# UI.net
KiCad netlist of a schematic drawn in Altium Designer
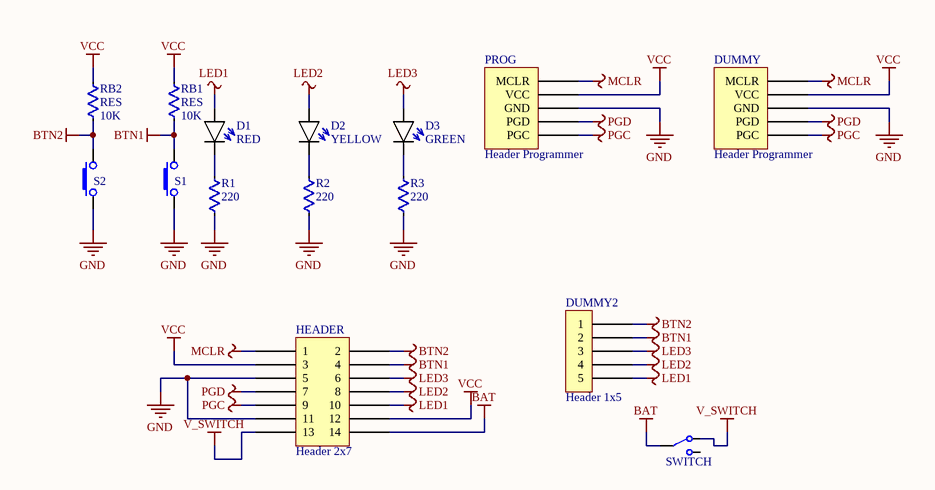
[diagram p0: UI.SchDoc]

(export (version "E")
  (design (tool "Eeschema 10.0.6"))
  (components
    (comp (ref "D1")
      (value "LED")
      (footprint "LED-3MM-RED")
      (fields (field (name "COLOR") "RED"))
      (libsource (lib "AltiumLibrary") (part "LED"))
    )
    (comp (ref "D2")
      (value "LED")
      (footprint "LED-3MM-YELLOW")
      (fields (field (name "COLOR") "YELLOW"))
      (libsource (lib "AltiumLibrary") (part "LED"))
    )
    (comp (ref "D3")
      (value "LED")
      (footprint "LED-3MM-GREEN")
      (fields (field (name "COLOR") "GREEN"))
      (libsource (lib "AltiumLibrary") (part "LED"))
    )
    (comp (ref "DUMMY")
      (value "Header Programmer")
      (footprint "Header 1x5")
      (libsource (lib "AltiumLibrary") (part "Header Programmer"))
    )
    (comp (ref "DUMMY2")
      (value "Header 1x5")
      (footprint "Header 1x5")
      (libsource (lib "AltiumLibrary") (part "Header 1x5"))
    )
    (comp (ref "HEADER")
      (value "Header 2x7")
      (footprint "HEADER 2x7")
      (libsource (lib "AltiumLibrary") (part "Header 2x7"))
    )
    (comp (ref "PROG")
      (value "Header Programmer")
      (footprint "Header 1x5")
      (libsource (lib "AltiumLibrary") (part "Header Programmer"))
    )
    (comp (ref "R1")
      (value "220")
      (footprint "RES-Axial-400mil")
      (fields (field (name "Comment") "RES"))
      (libsource (lib "AltiumLibrary") (part "RES"))
    )
    (comp (ref "R2")
      (value "220")
      (footprint "RES-Axial-400mil")
      (fields (field (name "Comment") "RES"))
      (libsource (lib "AltiumLibrary") (part "RES"))
    )
    (comp (ref "R3")
      (value "220")
      (footprint "RES-Axial-400mil")
      (fields (field (name "Comment") "RES"))
      (libsource (lib "AltiumLibrary") (part "RES"))
    )
    (comp (ref "RB1")
      (value "RES")
      (footprint "RES-Axial-400mil")
      (fields (field (name "ALTIUM_VALUE") "10K"))
      (libsource (lib "AltiumLibrary") (part "RES"))
    )
    (comp (ref "RB2")
      (value "RES")
      (footprint "RES-Axial-400mil")
      (fields (field (name "ALTIUM_VALUE") "10K"))
      (libsource (lib "AltiumLibrary") (part "RES"))
    )
    (comp (ref "S1")
      (value "BUTTON_SMALL_4PIN")
      (footprint "TACT_SWITCH-SMALL-4PIN")
      (libsource (lib "AltiumLibrary") (part "BUTTON_SMALL_4PIN"))
    )
    (comp (ref "S2")
      (value "BUTTON_SMALL_4PIN")
      (footprint "TACT_SWITCH-SMALL-4PIN")
      (libsource (lib "AltiumLibrary") (part "BUTTON_SMALL_4PIN"))
    )
    (comp (ref "SWITCH")
      (value "SLIDE-SWITCH")
      (footprint "SWITCH")
      (libsource (lib "AltiumLibrary") (part "SLIDE-SWITCH"))
    )
  )
  (nets
    (net (code "1") (name "BAT") (class "Default")
      (node (ref "HEADER") (pin "14") (pinfunction "14_14") (pintype "passive"))
      (node (ref "SWITCH") (pin "2") (pintype "power_in"))
    )
    (net (code "2") (name "BTN1") (class "Default")
      (node (ref "DUMMY2") (pin "2") (pinfunction "2_2") (pintype "passive"))
      (node (ref "HEADER") (pin "4") (pinfunction "4_4") (pintype "passive"))
      (node (ref "RB1") (pin "1") (pintype "passive"))
      (node (ref "S1") (pin "2") (pintype "passive"))
    )
    (net (code "3") (name "BTN2") (class "Default")
      (node (ref "DUMMY2") (pin "1") (pinfunction "1_1") (pintype "passive"))
      (node (ref "HEADER") (pin "2") (pinfunction "2_2") (pintype "passive"))
      (node (ref "RB2") (pin "1") (pintype "passive"))
      (node (ref "S2") (pin "2") (pintype "passive"))
    )
    (net (code "4") (name "GND") (class "Default")
      (node (ref "DUMMY") (pin "3") (pinfunction "GND_3") (pintype "power_in"))
      (node (ref "HEADER") (pin "11") (pinfunction "11_11") (pintype "passive"))
      (node (ref "HEADER") (pin "5") (pinfunction "5_5") (pintype "passive"))
      (node (ref "PROG") (pin "3") (pinfunction "GND_3") (pintype "power_in"))
      (node (ref "R1") (pin "1") (pintype "passive"))
      (node (ref "R2") (pin "1") (pintype "passive"))
      (node (ref "R3") (pin "1") (pintype "passive"))
      (node (ref "S1") (pin "1") (pintype "passive"))
      (node (ref "S2") (pin "1") (pintype "passive"))
    )
    (net (code "5") (name "LED1") (class "Default")
      (node (ref "D1") (pin "A") (pintype "passive"))
      (node (ref "DUMMY2") (pin "5") (pinfunction "5_5") (pintype "passive"))
      (node (ref "HEADER") (pin "10") (pinfunction "10_10") (pintype "passive"))
    )
    (net (code "6") (name "LED2") (class "Default")
      (node (ref "D2") (pin "A") (pintype "passive"))
      (node (ref "DUMMY2") (pin "4") (pinfunction "4_4") (pintype "passive"))
      (node (ref "HEADER") (pin "8") (pinfunction "8_8") (pintype "passive"))
    )
    (net (code "7") (name "LED3") (class "Default")
      (node (ref "D3") (pin "A") (pintype "passive"))
      (node (ref "DUMMY2") (pin "3") (pinfunction "3_3") (pintype "passive"))
      (node (ref "HEADER") (pin "6") (pinfunction "6_6") (pintype "passive"))
    )
    (net (code "8") (name "MCLR") (class "Default")
      (node (ref "DUMMY") (pin "1") (pinfunction "MCLR_1") (pintype "passive"))
      (node (ref "HEADER") (pin "1") (pinfunction "1_1") (pintype "passive"))
      (node (ref "PROG") (pin "1") (pinfunction "MCLR_1") (pintype "passive"))
    )
    (net (code "9") (name "Net-(D1-PadK)") (class "Default")
      (node (ref "D1") (pin "K") (pintype "passive"))
      (node (ref "R1") (pin "2") (pintype "passive"))
    )
    (net (code "10") (name "Net-(D2-PadK)") (class "Default")
      (node (ref "D2") (pin "K") (pintype "passive"))
      (node (ref "R2") (pin "2") (pintype "passive"))
    )
    (net (code "11") (name "Net-(D3-PadK)") (class "Default")
      (node (ref "D3") (pin "K") (pintype "passive"))
      (node (ref "R3") (pin "2") (pintype "passive"))
    )
    (net (code "12") (name "PGC") (class "Default")
      (node (ref "DUMMY") (pin "5") (pinfunction "PGC_5") (pintype "passive"))
      (node (ref "HEADER") (pin "9") (pinfunction "9_9") (pintype "passive"))
      (node (ref "PROG") (pin "5") (pinfunction "PGC_5") (pintype "passive"))
    )
    (net (code "13") (name "PGD") (class "Default")
      (node (ref "DUMMY") (pin "4") (pinfunction "PGD_4") (pintype "passive"))
      (node (ref "HEADER") (pin "7") (pinfunction "7_7") (pintype "passive"))
      (node (ref "PROG") (pin "4") (pinfunction "PGD_4") (pintype "passive"))
    )
    (net (code "14") (name "VCC") (class "Default")
      (node (ref "DUMMY") (pin "2") (pinfunction "VCC_2") (pintype "power_in"))
      (node (ref "HEADER") (pin "12") (pinfunction "12_12") (pintype "passive"))
      (node (ref "HEADER") (pin "3") (pinfunction "3_3") (pintype "passive"))
      (node (ref "PROG") (pin "2") (pinfunction "VCC_2") (pintype "power_in"))
      (node (ref "RB1") (pin "2") (pintype "passive"))
      (node (ref "RB2") (pin "2") (pintype "passive"))
    )
    (net (code "15") (name "V_SWITCH") (class "Default")
      (node (ref "HEADER") (pin "13") (pinfunction "13_13") (pintype "passive"))
      (node (ref "SWITCH") (pin "1") (pintype "power_in"))
    )
    (net (code "16") (name "unconnected-(SWITCH-Pad3)") (class "Default")
      (node (ref "SWITCH") (pin "3") (pintype "power_in"))
    )
  )
)
